# GPIO-I2C.net
KiCad netlist of a schematic drawn in Altium Designer
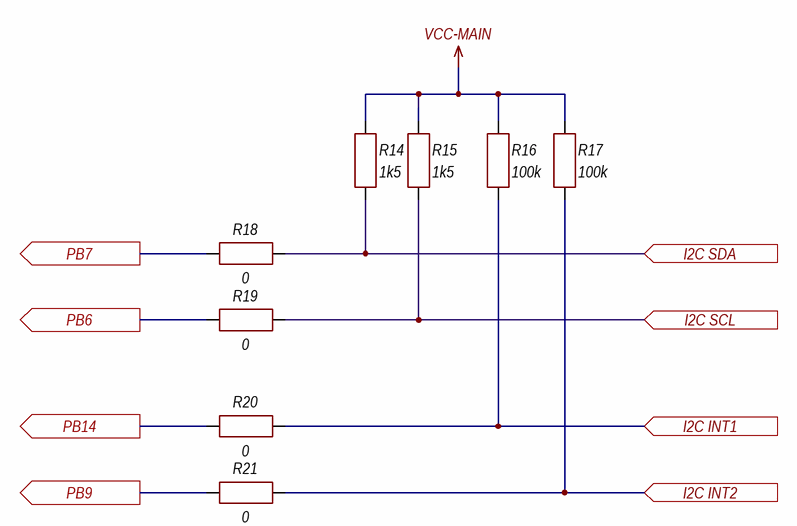
[diagram p0: GPIO-I2C.SchDoc]

(export (version "E")
  (design (tool "Eeschema 10.0.6"))
  (components
    (comp (ref "R14") (value "1k5") (footprint "CH0402R") (libsource (lib "") (part "Resistor_1")))
    (comp (ref "R15") (value "1k5") (footprint "CH0402R") (libsource (lib "") (part "Resistor_1")))
    (comp (ref "R16") (value "100k") (footprint "CH0402R") (libsource (lib "") (part "Resistor_1")))
    (comp (ref "R17") (value "100k") (footprint "CH0402R") (libsource (lib "") (part "Resistor_1")))
    (comp (ref "R18") (value "0") (footprint "CH0402R") (libsource (lib "Discrete") (part "Resistor")))
    (comp (ref "R19") (value "0") (footprint "CH0402R") (libsource (lib "Discrete") (part "Resistor")))
    (comp (ref "R20") (value "0") (footprint "CH0402R") (libsource (lib "Discrete") (part "Resistor")))
    (comp (ref "R21") (value "0") (footprint "CH0402R") (libsource (lib "Discrete") (part "Resistor")))
  )
  (nets
    (net (code "1") (name "/I2C INT1") (class "Default")
      (node (ref "R16") (pin "1") (pinfunction "1_1") (pintype "passive"))
      (node (ref "R20") (pin "2") (pinfunction "2_2") (pintype "passive"))
    )
    (net (code "2") (name "/I2C INT2") (class "Default")
      (node (ref "R17") (pin "1") (pinfunction "1_1") (pintype "passive"))
      (node (ref "R21") (pin "2") (pinfunction "2_2") (pintype "passive"))
    )
    (net (code "3") (name "/I2C SCL") (class "Default")
      (node (ref "R15") (pin "1") (pinfunction "1_1") (pintype "passive"))
      (node (ref "R19") (pin "2") (pinfunction "2_2") (pintype "passive"))
    )
    (net (code "4") (name "/I2C SDA") (class "Default")
      (node (ref "R14") (pin "1") (pinfunction "1_1") (pintype "passive"))
      (node (ref "R18") (pin "2") (pinfunction "2_2") (pintype "passive"))
    )
    (net (code "5") (name "/PB6") (class "Default")
      (node (ref "R19") (pin "1") (pinfunction "1_1") (pintype "passive"))
    )
    (net (code "6") (name "/PB7") (class "Default")
      (node (ref "R18") (pin "1") (pinfunction "1_1") (pintype "passive"))
    )
    (net (code "7") (name "/PB9") (class "Default")
      (node (ref "R21") (pin "1") (pinfunction "1_1") (pintype "passive"))
    )
    (net (code "8") (name "/PB14") (class "Default")
      (node (ref "R20") (pin "1") (pinfunction "1_1") (pintype "passive"))
    )
    (net (code "9") (name "VCC-MAIN") (class "Default")
      (node (ref "R14") (pin "2") (pinfunction "2_2") (pintype "passive"))
      (node (ref "R15") (pin "2") (pinfunction "2_2") (pintype "passive"))
      (node (ref "R16") (pin "2") (pinfunction "2_2") (pintype "passive"))
      (node (ref "R17") (pin "2") (pinfunction "2_2") (pintype "passive"))
    )
  )
)
